# Battery_board_V2.net
KiCad netlist of a schematic drawn in EAGLE
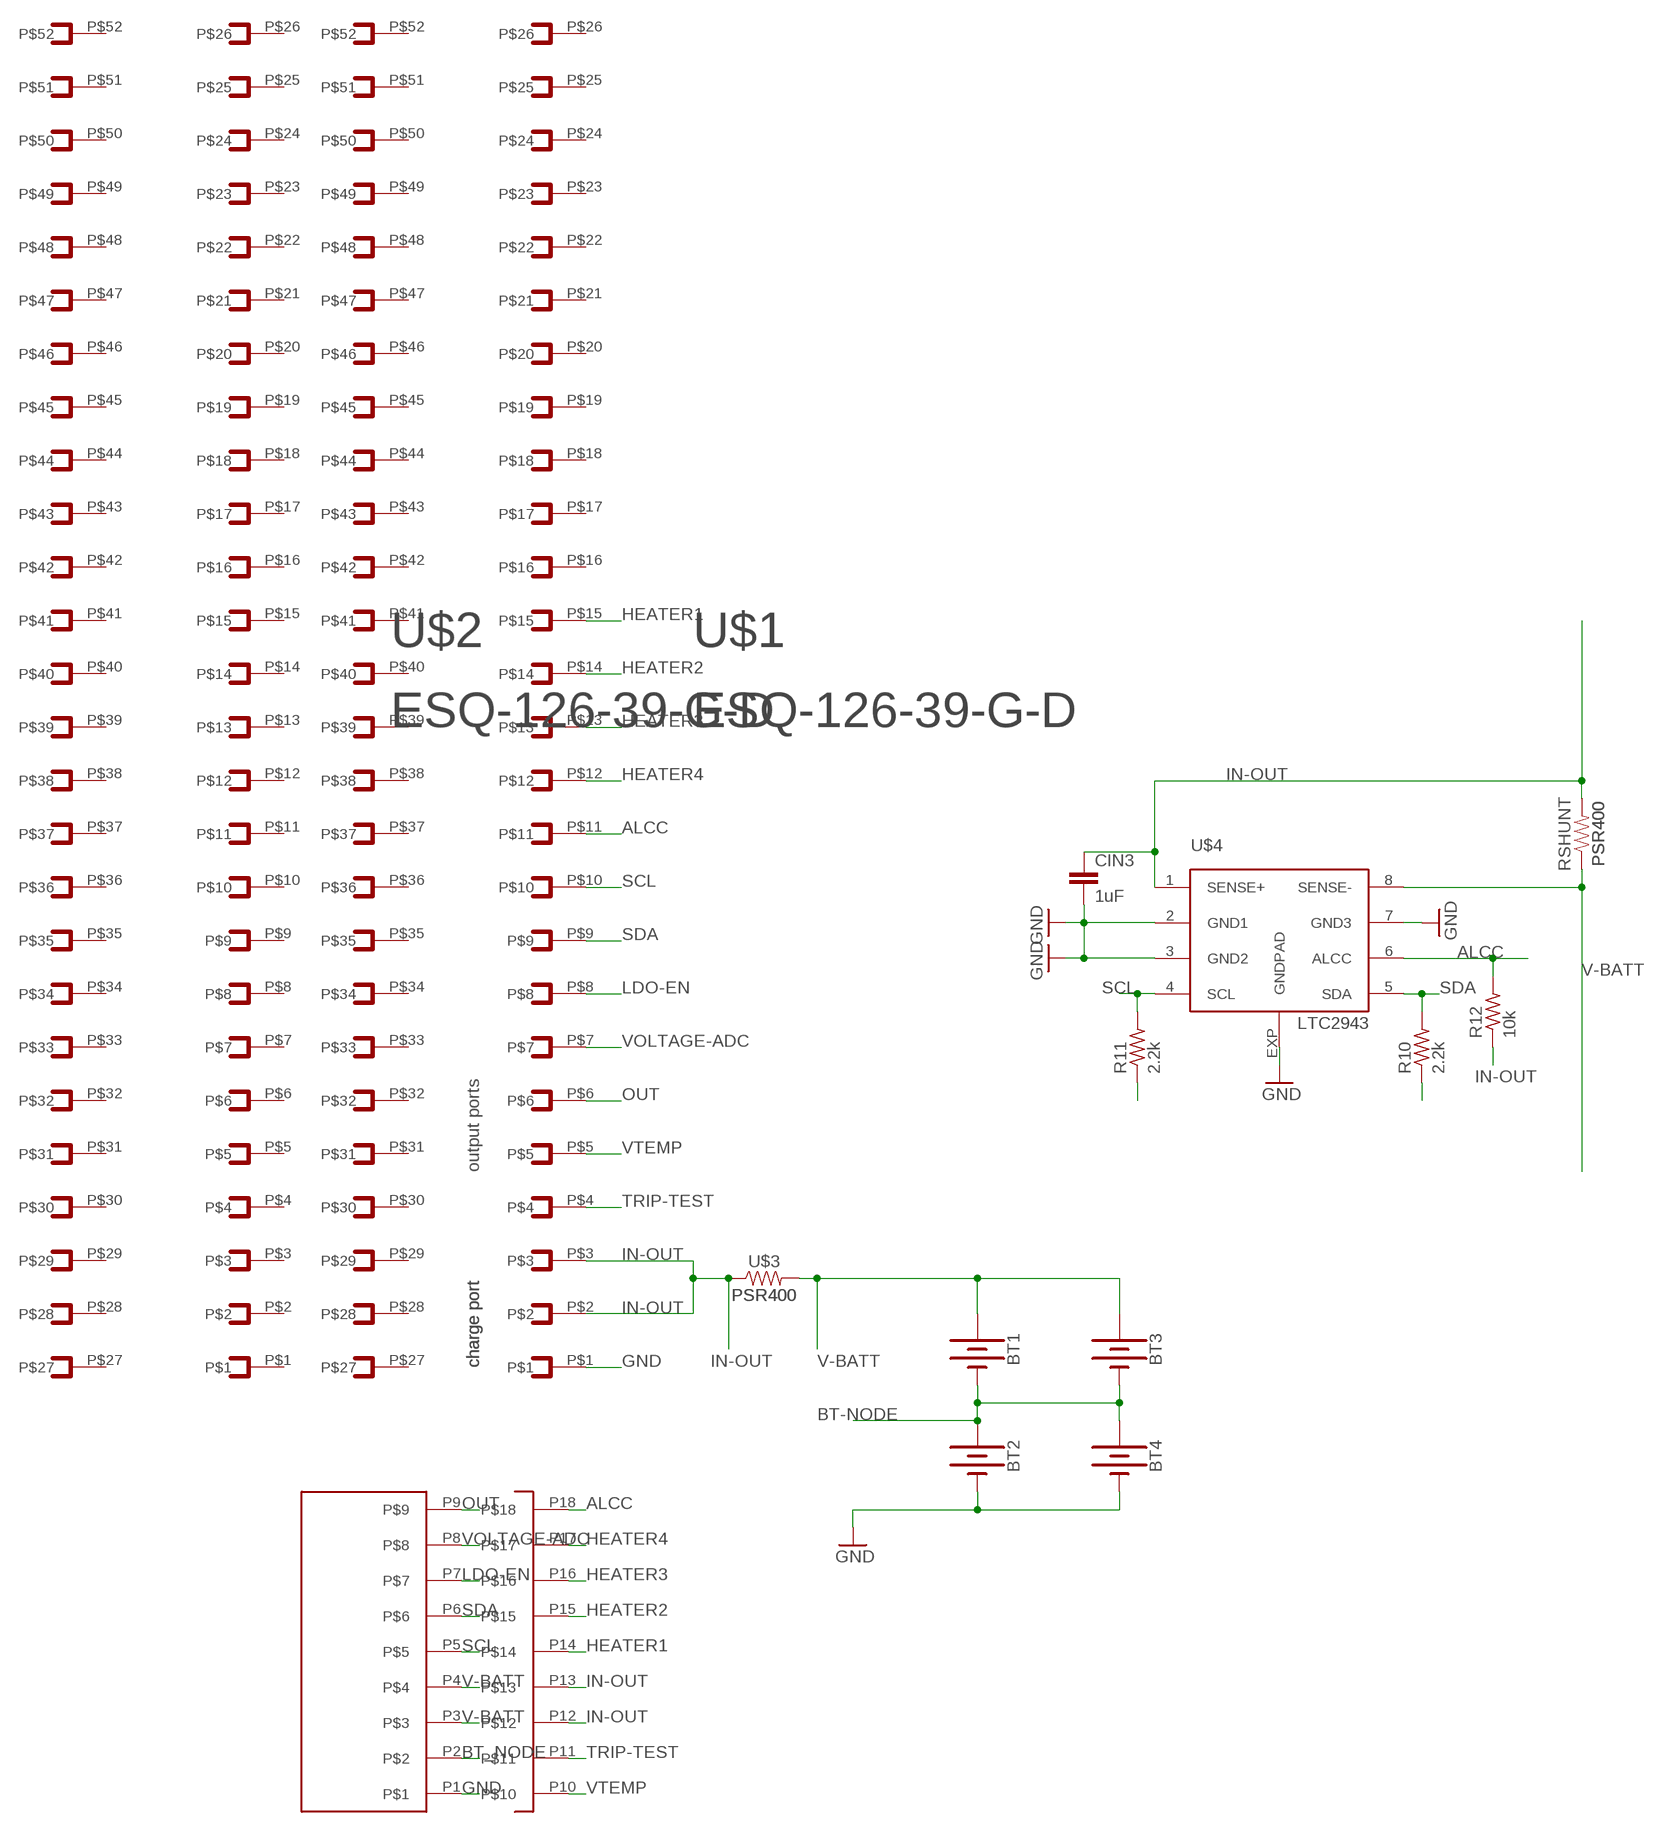
[diagram p0: schematic, sheet 1]

(export (version "E")
  (design (tool "Eeschema 10.0.6"))
  (components
    (comp (ref "BT1")
      (value "BATTERY-18650")
      (footprint "eagle-import:BATTERY_18650-HOLDER")
      (libsource (lib "eagle-import") (part "BATTERY-18650"))
    )
    (comp (ref "BT2")
      (value "BATTERY-18650")
      (footprint "eagle-import:BATTERY_18650-HOLDER")
      (libsource (lib "eagle-import") (part "BATTERY-18650"))
    )
    (comp (ref "BT3")
      (value "BATTERY-18650")
      (footprint "eagle-import:BATTERY_18650-HOLDER")
      (libsource (lib "eagle-import") (part "BATTERY-18650"))
    )
    (comp (ref "BT4")
      (value "BATTERY-18650")
      (footprint "eagle-import:BATTERY_18650-HOLDER")
      (libsource (lib "eagle-import") (part "BATTERY-18650"))
    )
    (comp (ref "CIN3")
      (value "1uF")
      (footprint "eagle-import:0402-CAP")
      (libsource (lib "eagle-import") (part ".1UF-CER"))
    )
    (comp (ref "R10")
      (value "2.2k")
      (footprint "eagle-import:R0805")
      (libsource (lib "eagle-import") (part "R-US_R0805"))
    )
    (comp (ref "R11")
      (value "2.2k")
      (footprint "eagle-import:R0805")
      (libsource (lib "eagle-import") (part "R-US_R0805"))
    )
    (comp (ref "R12")
      (value "10k")
      (footprint "eagle-import:R0805")
      (libsource (lib "eagle-import") (part "R-US_R0805"))
    )
    (comp (ref "RSHUNT")
      (value "PSR400")
      (footprint "eagle-import:PSR400")
      (libsource (lib "eagle-import") (part "PSR400"))
    )
    (comp (ref "U$1")
      (value "ESQ-126-39-G-D")
      (footprint "eagle-import:(RD)ESQ-126-39-G-D")
      (libsource (lib "eagle-import") (part "ESQ-126-39-G-D"))
    )
    (comp (ref "U$2")
      (value "ESQ-126-39-G-D")
      (footprint "eagle-import:(RD)ESQ-126-39-G-D")
      (libsource (lib "eagle-import") (part "ESQ-126-39-G-D"))
    )
    (comp (ref "U$3")
      (value "PSR400")
      (footprint "eagle-import:PSR400")
      (libsource (lib "eagle-import") (part "PSR400"))
    )
    (comp (ref "U$4")
      (value "LTC2943")
      (footprint "eagle-import:DFN8(3X3)LT")
      (libsource (lib "eagle-import") (part "LTC2943"))
    )
    (comp (ref "U$7")
      (value "FFC18")
      (footprint "eagle-import:FFC18")
      (libsource (lib "eagle-import") (part "FFC18"))
    )
  )
  (nets
    (net (code "1") (name "/ALCC") (class "Default")
      (node (ref "R12") (pin "2") (pinfunction "2_2") (pintype "passive"))
      (node (ref "U$1") (pin "P$11") (pinfunction "P$11_P$11") (pintype "bidirectional"))
      (node (ref "U$4") (pin "6") (pinfunction "ALCC_6") (pintype "bidirectional"))
      (node (ref "U$7") (pin "P18") (pinfunction "P$18_P18") (pintype "bidirectional"))
    )
    (net (code "2") (name "/BT-NODE") (class "Default")
      (node (ref "BT1") (pin "GND@1") (pinfunction "-_GND@1") (pintype "power_in"))
      (node (ref "BT2") (pin "PWR@1") (pinfunction "+_PWR@1") (pintype "power_in"))
      (node (ref "BT3") (pin "GND@1") (pinfunction "-_GND@1") (pintype "power_in"))
      (node (ref "BT4") (pin "PWR@1") (pinfunction "+_PWR@1") (pintype "power_in"))
    )
    (net (code "3") (name "/BT_NODE") (class "Default")
      (node (ref "U$7") (pin "P2") (pinfunction "P$2_P2") (pintype "bidirectional"))
    )
    (net (code "4") (name "/HEATER1") (class "Default")
      (node (ref "U$1") (pin "P$15") (pinfunction "P$15_P$15") (pintype "bidirectional"))
      (node (ref "U$7") (pin "P14") (pinfunction "P$14_P14") (pintype "bidirectional"))
    )
    (net (code "5") (name "/HEATER2") (class "Default")
      (node (ref "U$1") (pin "P$14") (pinfunction "P$14_P$14") (pintype "bidirectional"))
      (node (ref "U$7") (pin "P15") (pinfunction "P$15_P15") (pintype "bidirectional"))
    )
    (net (code "6") (name "/HEATER3") (class "Default")
      (node (ref "U$1") (pin "P$13") (pinfunction "P$13_P$13") (pintype "bidirectional"))
      (node (ref "U$7") (pin "P16") (pinfunction "P$16_P16") (pintype "bidirectional"))
    )
    (net (code "7") (name "/HEATER4") (class "Default")
      (node (ref "U$1") (pin "P$12") (pinfunction "P$12_P$12") (pintype "bidirectional"))
      (node (ref "U$7") (pin "P17") (pinfunction "P$17_P17") (pintype "bidirectional"))
    )
    (net (code "8") (name "/IN-OUT") (class "Default")
      (node (ref "CIN3") (pin "1") (pinfunction "1_1") (pintype "passive"))
      (node (ref "R10") (pin "1") (pinfunction "1_1") (pintype "passive"))
      (node (ref "R11") (pin "1") (pinfunction "1_1") (pintype "passive"))
      (node (ref "R12") (pin "1") (pinfunction "1_1") (pintype "passive"))
      (node (ref "RSHUNT") (pin "P$2") (pinfunction "2_P$2") (pintype "passive"))
      (node (ref "U$1") (pin "P$2") (pinfunction "P$2_P$2") (pintype "bidirectional"))
      (node (ref "U$1") (pin "P$3") (pinfunction "P$3_P$3") (pintype "bidirectional"))
      (node (ref "U$3") (pin "P$1") (pinfunction "1_P$1") (pintype "passive"))
      (node (ref "U$4") (pin "1") (pinfunction "SENSE+_1") (pintype "bidirectional"))
      (node (ref "U$7") (pin "P12") (pinfunction "P$12_P12") (pintype "bidirectional"))
      (node (ref "U$7") (pin "P13") (pinfunction "P$13_P13") (pintype "bidirectional"))
    )
    (net (code "9") (name "/LDO-EN") (class "Default")
      (node (ref "U$1") (pin "P$8") (pinfunction "P$8_P$8") (pintype "bidirectional"))
      (node (ref "U$7") (pin "P7") (pinfunction "P$7_P7") (pintype "bidirectional"))
    )
    (net (code "10") (name "/OUT") (class "Default")
      (node (ref "U$1") (pin "P$6") (pinfunction "P$6_P$6") (pintype "bidirectional"))
      (node (ref "U$7") (pin "P9") (pinfunction "P$9_P9") (pintype "bidirectional"))
    )
    (net (code "11") (name "/SCL") (class "Default")
      (node (ref "R11") (pin "2") (pinfunction "2_2") (pintype "passive"))
      (node (ref "U$1") (pin "P$10") (pinfunction "P$10_P$10") (pintype "bidirectional"))
      (node (ref "U$4") (pin "4") (pinfunction "SCL_4") (pintype "bidirectional"))
      (node (ref "U$7") (pin "P5") (pinfunction "P$5_P5") (pintype "bidirectional"))
    )
    (net (code "12") (name "/SDA") (class "Default")
      (node (ref "R10") (pin "2") (pinfunction "2_2") (pintype "passive"))
      (node (ref "U$1") (pin "P$9") (pinfunction "P$9_P$9") (pintype "bidirectional"))
      (node (ref "U$4") (pin "5") (pinfunction "SDA_5") (pintype "bidirectional"))
      (node (ref "U$7") (pin "P6") (pinfunction "P$6_P6") (pintype "bidirectional"))
    )
    (net (code "13") (name "/TRIP-TEST") (class "Default")
      (node (ref "U$1") (pin "P$4") (pinfunction "P$4_P$4") (pintype "bidirectional"))
      (node (ref "U$7") (pin "P11") (pinfunction "P$11_P11") (pintype "bidirectional"))
    )
    (net (code "14") (name "/V-BATT") (class "Default")
      (node (ref "BT1") (pin "PWR@1") (pinfunction "+_PWR@1") (pintype "power_in"))
      (node (ref "BT3") (pin "PWR@1") (pinfunction "+_PWR@1") (pintype "power_in"))
      (node (ref "RSHUNT") (pin "P$1") (pinfunction "1_P$1") (pintype "passive"))
      (node (ref "U$3") (pin "P$2") (pinfunction "2_P$2") (pintype "passive"))
      (node (ref "U$4") (pin "8") (pinfunction "SENSE-_8") (pintype "bidirectional"))
      (node (ref "U$7") (pin "P3") (pinfunction "P$3_P3") (pintype "bidirectional"))
      (node (ref "U$7") (pin "P4") (pinfunction "P$4_P4") (pintype "bidirectional"))
    )
    (net (code "15") (name "/VOLTAGE-ADC") (class "Default")
      (node (ref "U$1") (pin "P$7") (pinfunction "P$7_P$7") (pintype "bidirectional"))
      (node (ref "U$7") (pin "P8") (pinfunction "P$8_P8") (pintype "bidirectional"))
    )
    (net (code "16") (name "/VTEMP") (class "Default")
      (node (ref "U$1") (pin "P$5") (pinfunction "P$5_P$5") (pintype "bidirectional"))
      (node (ref "U$7") (pin "P10") (pinfunction "P$10_P10") (pintype "bidirectional"))
    )
    (net (code "17") (name "GND") (class "Default")
      (node (ref "BT2") (pin "GND@1") (pinfunction "-_GND@1") (pintype "power_in"))
      (node (ref "BT4") (pin "GND@1") (pinfunction "-_GND@1") (pintype "power_in"))
      (node (ref "CIN3") (pin "2") (pinfunction "2_2") (pintype "passive"))
      (node (ref "U$1") (pin "P$1") (pinfunction "P$1_P$1") (pintype "bidirectional"))
      (node (ref "U$4") (pin "2") (pinfunction "GND1_2") (pintype "bidirectional"))
      (node (ref "U$4") (pin "3") (pinfunction "GND2_3") (pintype "bidirectional"))
      (node (ref "U$4") (pin "7") (pinfunction "GND3_7") (pintype "bidirectional"))
      (node (ref "U$4") (pin "EXP") (pinfunction "GNDPAD_EXP") (pintype "bidirectional"))
      (node (ref "U$7") (pin "P1") (pinfunction "P$1_P1") (pintype "bidirectional"))
    )
    (net (code "18") (name "unconnected-(U$1-PadP$16)") (class "Default")
      (node (ref "U$1") (pin "P$16") (pinfunction "P$16_P$16") (pintype "bidirectional"))
    )
    (net (code "19") (name "unconnected-(U$1-PadP$17)") (class "Default")
      (node (ref "U$1") (pin "P$17") (pinfunction "P$17_P$17") (pintype "bidirectional"))
    )
    (net (code "20") (name "unconnected-(U$1-PadP$18)") (class "Default")
      (node (ref "U$1") (pin "P$18") (pinfunction "P$18_P$18") (pintype "bidirectional"))
    )
    (net (code "21") (name "unconnected-(U$1-PadP$19)") (class "Default")
      (node (ref "U$1") (pin "P$19") (pinfunction "P$19_P$19") (pintype "bidirectional"))
    )
    (net (code "22") (name "unconnected-(U$1-PadP$20)") (class "Default")
      (node (ref "U$1") (pin "P$20") (pinfunction "P$20_P$20") (pintype "bidirectional"))
    )
    (net (code "23") (name "unconnected-(U$1-PadP$21)") (class "Default")
      (node (ref "U$1") (pin "P$21") (pinfunction "P$21_P$21") (pintype "bidirectional"))
    )
    (net (code "24") (name "unconnected-(U$1-PadP$22)") (class "Default")
      (node (ref "U$1") (pin "P$22") (pinfunction "P$22_P$22") (pintype "bidirectional"))
    )
    (net (code "25") (name "unconnected-(U$1-PadP$23)") (class "Default")
      (node (ref "U$1") (pin "P$23") (pinfunction "P$23_P$23") (pintype "bidirectional"))
    )
    (net (code "26") (name "unconnected-(U$1-PadP$24)") (class "Default")
      (node (ref "U$1") (pin "P$24") (pinfunction "P$24_P$24") (pintype "bidirectional"))
    )
    (net (code "27") (name "unconnected-(U$1-PadP$25)") (class "Default")
      (node (ref "U$1") (pin "P$25") (pinfunction "P$25_P$25") (pintype "bidirectional"))
    )
    (net (code "28") (name "unconnected-(U$1-PadP$26)") (class "Default")
      (node (ref "U$1") (pin "P$26") (pinfunction "P$26_P$26") (pintype "bidirectional"))
    )
    (net (code "29") (name "unconnected-(U$1-PadP$27)") (class "Default")
      (node (ref "U$1") (pin "P$27") (pinfunction "P$27_P$27") (pintype "bidirectional"))
    )
    (net (code "30") (name "unconnected-(U$1-PadP$28)") (class "Default")
      (node (ref "U$1") (pin "P$28") (pinfunction "P$28_P$28") (pintype "bidirectional"))
    )
    (net (code "31") (name "unconnected-(U$1-PadP$29)") (class "Default")
      (node (ref "U$1") (pin "P$29") (pinfunction "P$29_P$29") (pintype "bidirectional"))
    )
    (net (code "32") (name "unconnected-(U$1-PadP$30)") (class "Default")
      (node (ref "U$1") (pin "P$30") (pinfunction "P$30_P$30") (pintype "bidirectional"))
    )
    (net (code "33") (name "unconnected-(U$1-PadP$31)") (class "Default")
      (node (ref "U$1") (pin "P$31") (pinfunction "P$31_P$31") (pintype "bidirectional"))
    )
    (net (code "34") (name "unconnected-(U$1-PadP$32)") (class "Default")
      (node (ref "U$1") (pin "P$32") (pinfunction "P$32_P$32") (pintype "bidirectional"))
    )
    (net (code "35") (name "unconnected-(U$1-PadP$33)") (class "Default")
      (node (ref "U$1") (pin "P$33") (pinfunction "P$33_P$33") (pintype "bidirectional"))
    )
    (net (code "36") (name "unconnected-(U$1-PadP$34)") (class "Default")
      (node (ref "U$1") (pin "P$34") (pinfunction "P$34_P$34") (pintype "bidirectional"))
    )
    (net (code "37") (name "unconnected-(U$1-PadP$35)") (class "Default")
      (node (ref "U$1") (pin "P$35") (pinfunction "P$35_P$35") (pintype "bidirectional"))
    )
    (net (code "38") (name "unconnected-(U$1-PadP$36)") (class "Default")
      (node (ref "U$1") (pin "P$36") (pinfunction "P$36_P$36") (pintype "bidirectional"))
    )
    (net (code "39") (name "unconnected-(U$1-PadP$37)") (class "Default")
      (node (ref "U$1") (pin "P$37") (pinfunction "P$37_P$37") (pintype "bidirectional"))
    )
    (net (code "40") (name "unconnected-(U$1-PadP$38)") (class "Default")
      (node (ref "U$1") (pin "P$38") (pinfunction "P$38_P$38") (pintype "bidirectional"))
    )
    (net (code "41") (name "unconnected-(U$1-PadP$39)") (class "Default")
      (node (ref "U$1") (pin "P$39") (pinfunction "P$39_P$39") (pintype "bidirectional"))
    )
    (net (code "42") (name "unconnected-(U$1-PadP$40)") (class "Default")
      (node (ref "U$1") (pin "P$40") (pinfunction "P$40_P$40") (pintype "bidirectional"))
    )
    (net (code "43") (name "unconnected-(U$1-PadP$41)") (class "Default")
      (node (ref "U$1") (pin "P$41") (pinfunction "P$41_P$41") (pintype "bidirectional"))
    )
    (net (code "44") (name "unconnected-(U$1-PadP$42)") (class "Default")
      (node (ref "U$1") (pin "P$42") (pinfunction "P$42_P$42") (pintype "bidirectional"))
    )
    (net (code "45") (name "unconnected-(U$1-PadP$43)") (class "Default")
      (node (ref "U$1") (pin "P$43") (pinfunction "P$43_P$43") (pintype "bidirectional"))
    )
    (net (code "46") (name "unconnected-(U$1-PadP$44)") (class "Default")
      (node (ref "U$1") (pin "P$44") (pinfunction "P$44_P$44") (pintype "bidirectional"))
    )
    (net (code "47") (name "unconnected-(U$1-PadP$45)") (class "Default")
      (node (ref "U$1") (pin "P$45") (pinfunction "P$45_P$45") (pintype "bidirectional"))
    )
    (net (code "48") (name "unconnected-(U$1-PadP$46)") (class "Default")
      (node (ref "U$1") (pin "P$46") (pinfunction "P$46_P$46") (pintype "bidirectional"))
    )
    (net (code "49") (name "unconnected-(U$1-PadP$47)") (class "Default")
      (node (ref "U$1") (pin "P$47") (pinfunction "P$47_P$47") (pintype "bidirectional"))
    )
    (net (code "50") (name "unconnected-(U$1-PadP$48)") (class "Default")
      (node (ref "U$1") (pin "P$48") (pinfunction "P$48_P$48") (pintype "bidirectional"))
    )
    (net (code "51") (name "unconnected-(U$1-PadP$49)") (class "Default")
      (node (ref "U$1") (pin "P$49") (pinfunction "P$49_P$49") (pintype "bidirectional"))
    )
    (net (code "52") (name "unconnected-(U$1-PadP$50)") (class "Default")
      (node (ref "U$1") (pin "P$50") (pinfunction "P$50_P$50") (pintype "bidirectional"))
    )
    (net (code "53") (name "unconnected-(U$1-PadP$51)") (class "Default")
      (node (ref "U$1") (pin "P$51") (pinfunction "P$51_P$51") (pintype "bidirectional"))
    )
    (net (code "54") (name "unconnected-(U$1-PadP$52)") (class "Default")
      (node (ref "U$1") (pin "P$52") (pinfunction "P$52_P$52") (pintype "bidirectional"))
    )
    (net (code "55") (name "unconnected-(U$2-PadP$1)") (class "Default")
      (node (ref "U$2") (pin "P$1") (pinfunction "P$1_P$1") (pintype "bidirectional"))
    )
    (net (code "56") (name "unconnected-(U$2-PadP$2)") (class "Default")
      (node (ref "U$2") (pin "P$2") (pinfunction "P$2_P$2") (pintype "bidirectional"))
    )
    (net (code "57") (name "unconnected-(U$2-PadP$3)") (class "Default")
      (node (ref "U$2") (pin "P$3") (pinfunction "P$3_P$3") (pintype "bidirectional"))
    )
    (net (code "58") (name "unconnected-(U$2-PadP$4)") (class "Default")
      (node (ref "U$2") (pin "P$4") (pinfunction "P$4_P$4") (pintype "bidirectional"))
    )
    (net (code "59") (name "unconnected-(U$2-PadP$5)") (class "Default")
      (node (ref "U$2") (pin "P$5") (pinfunction "P$5_P$5") (pintype "bidirectional"))
    )
    (net (code "60") (name "unconnected-(U$2-PadP$6)") (class "Default")
      (node (ref "U$2") (pin "P$6") (pinfunction "P$6_P$6") (pintype "bidirectional"))
    )
    (net (code "61") (name "unconnected-(U$2-PadP$7)") (class "Default")
      (node (ref "U$2") (pin "P$7") (pinfunction "P$7_P$7") (pintype "bidirectional"))
    )
    (net (code "62") (name "unconnected-(U$2-PadP$8)") (class "Default")
      (node (ref "U$2") (pin "P$8") (pinfunction "P$8_P$8") (pintype "bidirectional"))
    )
    (net (code "63") (name "unconnected-(U$2-PadP$9)") (class "Default")
      (node (ref "U$2") (pin "P$9") (pinfunction "P$9_P$9") (pintype "bidirectional"))
    )
    (net (code "64") (name "unconnected-(U$2-PadP$10)") (class "Default")
      (node (ref "U$2") (pin "P$10") (pinfunction "P$10_P$10") (pintype "bidirectional"))
    )
    (net (code "65") (name "unconnected-(U$2-PadP$11)") (class "Default")
      (node (ref "U$2") (pin "P$11") (pinfunction "P$11_P$11") (pintype "bidirectional"))
    )
    (net (code "66") (name "unconnected-(U$2-PadP$12)") (class "Default")
      (node (ref "U$2") (pin "P$12") (pinfunction "P$12_P$12") (pintype "bidirectional"))
    )
    (net (code "67") (name "unconnected-(U$2-PadP$13)") (class "Default")
      (node (ref "U$2") (pin "P$13") (pinfunction "P$13_P$13") (pintype "bidirectional"))
    )
    (net (code "68") (name "unconnected-(U$2-PadP$14)") (class "Default")
      (node (ref "U$2") (pin "P$14") (pinfunction "P$14_P$14") (pintype "bidirectional"))
    )
    (net (code "69") (name "unconnected-(U$2-PadP$15)") (class "Default")
      (node (ref "U$2") (pin "P$15") (pinfunction "P$15_P$15") (pintype "bidirectional"))
    )
    (net (code "70") (name "unconnected-(U$2-PadP$16)") (class "Default")
      (node (ref "U$2") (pin "P$16") (pinfunction "P$16_P$16") (pintype "bidirectional"))
    )
    (net (code "71") (name "unconnected-(U$2-PadP$17)") (class "Default")
      (node (ref "U$2") (pin "P$17") (pinfunction "P$17_P$17") (pintype "bidirectional"))
    )
    (net (code "72") (name "unconnected-(U$2-PadP$18)") (class "Default")
      (node (ref "U$2") (pin "P$18") (pinfunction "P$18_P$18") (pintype "bidirectional"))
    )
    (net (code "73") (name "unconnected-(U$2-PadP$19)") (class "Default")
      (node (ref "U$2") (pin "P$19") (pinfunction "P$19_P$19") (pintype "bidirectional"))
    )
    (net (code "74") (name "unconnected-(U$2-PadP$20)") (class "Default")
      (node (ref "U$2") (pin "P$20") (pinfunction "P$20_P$20") (pintype "bidirectional"))
    )
    (net (code "75") (name "unconnected-(U$2-PadP$21)") (class "Default")
      (node (ref "U$2") (pin "P$21") (pinfunction "P$21_P$21") (pintype "bidirectional"))
    )
    (net (code "76") (name "unconnected-(U$2-PadP$22)") (class "Default")
      (node (ref "U$2") (pin "P$22") (pinfunction "P$22_P$22") (pintype "bidirectional"))
    )
    (net (code "77") (name "unconnected-(U$2-PadP$23)") (class "Default")
      (node (ref "U$2") (pin "P$23") (pinfunction "P$23_P$23") (pintype "bidirectional"))
    )
    (net (code "78") (name "unconnected-(U$2-PadP$24)") (class "Default")
      (node (ref "U$2") (pin "P$24") (pinfunction "P$24_P$24") (pintype "bidirectional"))
    )
    (net (code "79") (name "unconnected-(U$2-PadP$25)") (class "Default")
      (node (ref "U$2") (pin "P$25") (pinfunction "P$25_P$25") (pintype "bidirectional"))
    )
    (net (code "80") (name "unconnected-(U$2-PadP$26)") (class "Default")
      (node (ref "U$2") (pin "P$26") (pinfunction "P$26_P$26") (pintype "bidirectional"))
    )
    (net (code "81") (name "unconnected-(U$2-PadP$27)") (class "Default")
      (node (ref "U$2") (pin "P$27") (pinfunction "P$27_P$27") (pintype "bidirectional"))
    )
    (net (code "82") (name "unconnected-(U$2-PadP$28)") (class "Default")
      (node (ref "U$2") (pin "P$28") (pinfunction "P$28_P$28") (pintype "bidirectional"))
    )
    (net (code "83") (name "unconnected-(U$2-PadP$29)") (class "Default")
      (node (ref "U$2") (pin "P$29") (pinfunction "P$29_P$29") (pintype "bidirectional"))
    )
    (net (code "84") (name "unconnected-(U$2-PadP$30)") (class "Default")
      (node (ref "U$2") (pin "P$30") (pinfunction "P$30_P$30") (pintype "bidirectional"))
    )
    (net (code "85") (name "unconnected-(U$2-PadP$31)") (class "Default")
      (node (ref "U$2") (pin "P$31") (pinfunction "P$31_P$31") (pintype "bidirectional"))
    )
    (net (code "86") (name "unconnected-(U$2-PadP$32)") (class "Default")
      (node (ref "U$2") (pin "P$32") (pinfunction "P$32_P$32") (pintype "bidirectional"))
    )
    (net (code "87") (name "unconnected-(U$2-PadP$33)") (class "Default")
      (node (ref "U$2") (pin "P$33") (pinfunction "P$33_P$33") (pintype "bidirectional"))
    )
    (net (code "88") (name "unconnected-(U$2-PadP$34)") (class "Default")
      (node (ref "U$2") (pin "P$34") (pinfunction "P$34_P$34") (pintype "bidirectional"))
    )
    (net (code "89") (name "unconnected-(U$2-PadP$35)") (class "Default")
      (node (ref "U$2") (pin "P$35") (pinfunction "P$35_P$35") (pintype "bidirectional"))
    )
    (net (code "90") (name "unconnected-(U$2-PadP$36)") (class "Default")
      (node (ref "U$2") (pin "P$36") (pinfunction "P$36_P$36") (pintype "bidirectional"))
    )
    (net (code "91") (name "unconnected-(U$2-PadP$37)") (class "Default")
      (node (ref "U$2") (pin "P$37") (pinfunction "P$37_P$37") (pintype "bidirectional"))
    )
    (net (code "92") (name "unconnected-(U$2-PadP$38)") (class "Default")
      (node (ref "U$2") (pin "P$38") (pinfunction "P$38_P$38") (pintype "bidirectional"))
    )
    (net (code "93") (name "unconnected-(U$2-PadP$39)") (class "Default")
      (node (ref "U$2") (pin "P$39") (pinfunction "P$39_P$39") (pintype "bidirectional"))
    )
    (net (code "94") (name "unconnected-(U$2-PadP$40)") (class "Default")
      (node (ref "U$2") (pin "P$40") (pinfunction "P$40_P$40") (pintype "bidirectional"))
    )
    (net (code "95") (name "unconnected-(U$2-PadP$41)") (class "Default")
      (node (ref "U$2") (pin "P$41") (pinfunction "P$41_P$41") (pintype "bidirectional"))
    )
    (net (code "96") (name "unconnected-(U$2-PadP$42)") (class "Default")
      (node (ref "U$2") (pin "P$42") (pinfunction "P$42_P$42") (pintype "bidirectional"))
    )
    (net (code "97") (name "unconnected-(U$2-PadP$43)") (class "Default")
      (node (ref "U$2") (pin "P$43") (pinfunction "P$43_P$43") (pintype "bidirectional"))
    )
    (net (code "98") (name "unconnected-(U$2-PadP$44)") (class "Default")
      (node (ref "U$2") (pin "P$44") (pinfunction "P$44_P$44") (pintype "bidirectional"))
    )
    (net (code "99") (name "unconnected-(U$2-PadP$45)") (class "Default")
      (node (ref "U$2") (pin "P$45") (pinfunction "P$45_P$45") (pintype "bidirectional"))
    )
    (net (code "100") (name "unconnected-(U$2-PadP$46)") (class "Default")
      (node (ref "U$2") (pin "P$46") (pinfunction "P$46_P$46") (pintype "bidirectional"))
    )
    (net (code "101") (name "unconnected-(U$2-PadP$47)") (class "Default")
      (node (ref "U$2") (pin "P$47") (pinfunction "P$47_P$47") (pintype "bidirectional"))
    )
    (net (code "102") (name "unconnected-(U$2-PadP$48)") (class "Default")
      (node (ref "U$2") (pin "P$48") (pinfunction "P$48_P$48") (pintype "bidirectional"))
    )
    (net (code "103") (name "unconnected-(U$2-PadP$49)") (class "Default")
      (node (ref "U$2") (pin "P$49") (pinfunction "P$49_P$49") (pintype "bidirectional"))
    )
    (net (code "104") (name "unconnected-(U$2-PadP$50)") (class "Default")
      (node (ref "U$2") (pin "P$50") (pinfunction "P$50_P$50") (pintype "bidirectional"))
    )
    (net (code "105") (name "unconnected-(U$2-PadP$51)") (class "Default")
      (node (ref "U$2") (pin "P$51") (pinfunction "P$51_P$51") (pintype "bidirectional"))
    )
    (net (code "106") (name "unconnected-(U$2-PadP$52)") (class "Default")
      (node (ref "U$2") (pin "P$52") (pinfunction "P$52_P$52") (pintype "bidirectional"))
    )
  )
)
